# ESC.net
KiCad netlist of a schematic drawn in Altium Designer
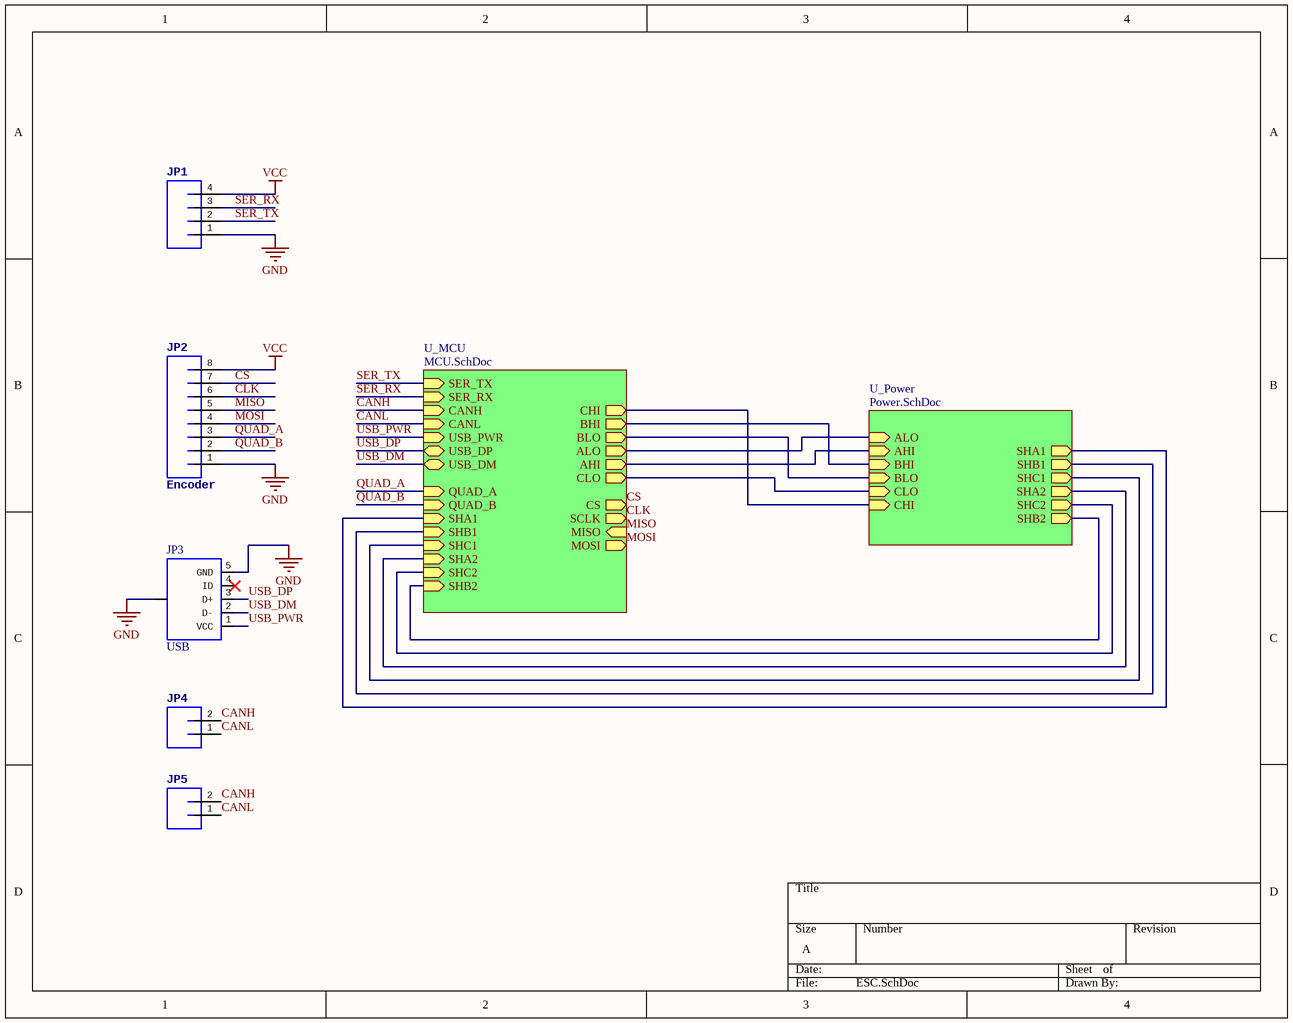
[diagram p0: ESC.SchDoc]

(export (version "E")
  (design (tool "Eeschema 10.0.6"))
  (components
    (comp (ref "JP1")
      (value "~")
      (footprint "JST-4-PTH-VERT")
      (libsource (lib "Components") (part "JST_4_VERT"))
    )
    (comp (ref "JP2")
      (value "Encoder")
      (footprint "JST-8-PTH-VERT")
      (libsource (lib "Components") (part "JST_8_VERT"))
    )
    (comp (ref "JP3")
      (value "USB")
      (footprint "USB-MICROB")
      (libsource (lib "Components") (part "USB_MICROB_PLUG-SMT"))
    )
    (comp (ref "JP4")
      (value "~")
      (footprint "JST-2-PTH-VERT")
      (libsource (lib "Components") (part "JST_2_VERT"))
    )
    (comp (ref "JP5")
      (value "~")
      (footprint "JST-2-PTH-VERT")
      (libsource (lib "Components") (part "JST_2_VERT"))
    )
  )
  (nets
    (net (code "5") (name "/CANH") (class "Default")
      (node (ref "JP4") (pin "2") (pinfunction "2_2") (pintype "passive"))
      (node (ref "JP5") (pin "2") (pinfunction "2_2") (pintype "passive"))
    )
    (net (code "6") (name "/CANL") (class "Default")
      (node (ref "JP4") (pin "1") (pinfunction "1_1") (pintype "passive"))
      (node (ref "JP5") (pin "1") (pinfunction "1_1") (pintype "passive"))
    )
    (net (code "8") (name "/CLK") (class "Default")
      (node (ref "JP2") (pin "6") (pinfunction "6_6") (pintype "passive"))
    )
    (net (code "10") (name "/CS") (class "Default")
      (node (ref "JP2") (pin "7") (pinfunction "7_7") (pintype "passive"))
    )
    (net (code "11") (name "/MISO") (class "Default")
      (node (ref "JP2") (pin "5") (pinfunction "5_5") (pintype "passive"))
    )
    (net (code "12") (name "/MOSI") (class "Default")
      (node (ref "JP2") (pin "4") (pinfunction "4_4") (pintype "passive"))
    )
    (net (code "13") (name "/QUAD_A") (class "Default")
      (node (ref "JP2") (pin "3") (pinfunction "3_3") (pintype "passive"))
    )
    (net (code "14") (name "/QUAD_B") (class "Default")
      (node (ref "JP2") (pin "2") (pinfunction "2_2") (pintype "passive"))
    )
    (net (code "15") (name "/SER_RX") (class "Default")
      (node (ref "JP1") (pin "3") (pinfunction "3_3") (pintype "passive"))
    )
    (net (code "16") (name "/SER_TX") (class "Default")
      (node (ref "JP1") (pin "2") (pinfunction "2_2") (pintype "passive"))
    )
    (net (code "23") (name "/USB_DM") (class "Default")
      (node (ref "JP3") (pin "2") (pinfunction "D-_2") (pintype "passive"))
    )
    (net (code "24") (name "/USB_DP") (class "Default")
      (node (ref "JP3") (pin "3") (pinfunction "D+_3") (pintype "passive"))
    )
    (net (code "25") (name "/USB_PWR") (class "Default")
      (node (ref "JP3") (pin "1") (pinfunction "VCC_1") (pintype "passive"))
    )
    (net (code "26") (name "GND") (class "Default")
      (node (ref "JP1") (pin "1") (pinfunction "1_1") (pintype "passive"))
      (node (ref "JP2") (pin "1") (pinfunction "1_1") (pintype "passive"))
      (node (ref "JP3") (pin "5") (pinfunction "GND_5") (pintype "passive"))
      (node (ref "JP3") (pin "6") (pinfunction "SHIELD_6") (pintype "passive"))
    )
    (net (code "27") (name "VCC") (class "Default")
      (node (ref "JP1") (pin "4") (pinfunction "4_4") (pintype "passive"))
      (node (ref "JP2") (pin "8") (pinfunction "8_8") (pintype "passive"))
    )
    (net (code "28") (name "unconnected-(JP3-ID-Pad4)") (class "Default")
      (node (ref "JP3") (pin "4") (pinfunction "ID_4") (pintype "passive+no_connect"))
    )
  )
)
